# Auxiliary_Regulators.net
KiCad netlist of a schematic drawn in Altium Designer
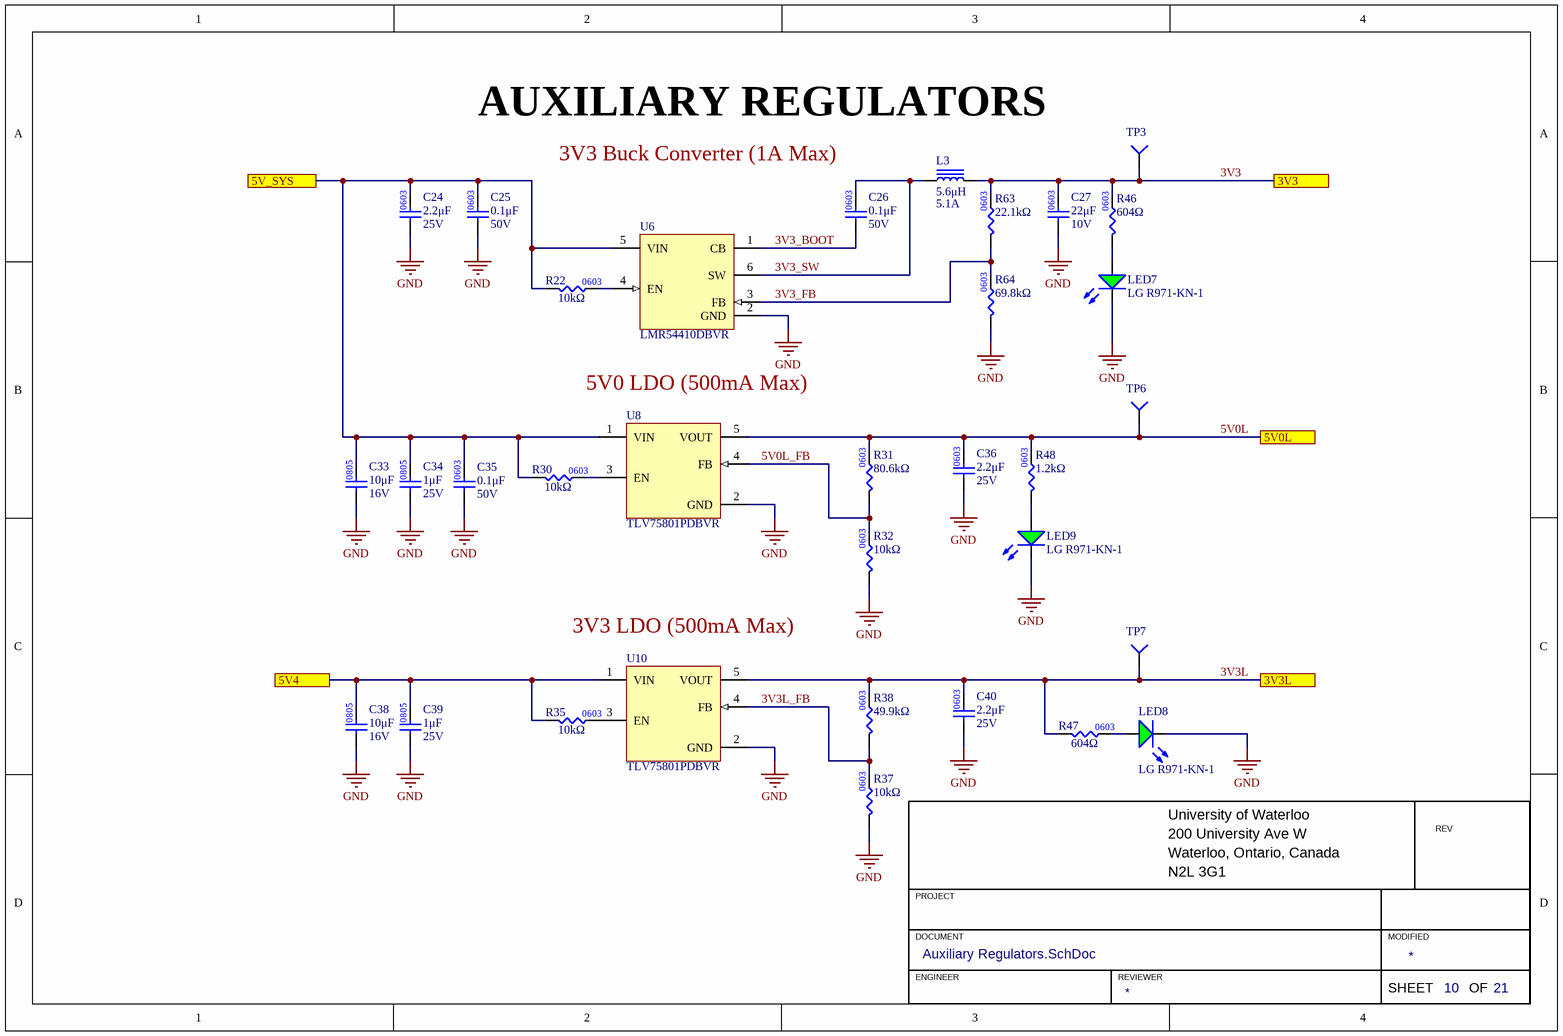
[diagram p0: Auxiliary Regulators.SchDoc]

(export (version "E")
  (design (tool "Eeschema 10.0.6"))
  (components
    (comp (ref "C24")
      (value "2.2μF")
      (footprint "CAP0603")
      (description "CAP CER 2.2UF 25V X5R 0603")
      (fields (field (name "VOLTAGE RATING") "25V") (field (name "Comment") "CAP_2.2uF_25V_0603"))
      (libsource (lib "Personal_Schematic_Library_2022") (part "CAP_2.2uF_25V_0603"))
    )
    (comp (ref "C25")
      (value "0.1μF")
      (footprint "CAP0603")
      (description "CAP CER 0.1UF 50V X7R 0603")
      (fields (field (name "VOLTAGE RATING") "50V") (field (name "Comment") "CAP_0.1uF_50V_0603"))
      (libsource (lib "Personal_Schematic_Library_2022") (part "CAP_0.1uF_50V_0603"))
    )
    (comp (ref "C26")
      (value "0.1μF")
      (footprint "CAP0603")
      (description "CAP CER 0.1UF 50V X7R 0603")
      (fields (field (name "VOLTAGE RATING") "50V") (field (name "Comment") "CAP_0.1uF_50V_0603"))
      (libsource (lib "Personal_Schematic_Library_2022") (part "CAP_0.1uF_50V_0603"))
    )
    (comp (ref "C27")
      (value "22μF")
      (footprint "CAP0603")
      (description "CAP CER 22UF 10V X5R 0603")
      (fields
        (field (name "MANUFACTURER") "Taiyo Yuden")
        (field (name "MANUFACTURER PART NUMBER") "LMK107BBJ226MA-T")
        (field (name "VOLTAGE RATING") "10V")
      )
      (libsource (lib "Personal_Schematic_Library_2022") (part "CAP_22uF_10V_0603"))
    )
    (comp (ref "C33")
      (value "10μF")
      (footprint "CAP0805")
      (description "CAP CER 10UF 16V X5R 0805")
      (fields (field (name "VOLTAGE RATING") "16V") (field (name "Comment") "CAP_10uF_16V_0805"))
      (libsource (lib "Personal_Schematic_Library_2022") (part "CAP_10uF_16V_0805"))
    )
    (comp (ref "C34")
      (value "1μF")
      (footprint "CAP0805")
      (description "CAP CER 1UF 25V X7R 0805")
      (fields (field (name "VOLTAGE RATING") "25V") (field (name "Comment") "CAP_1uF_25V_0805"))
      (libsource (lib "Personal_Schematic_Library_2022") (part "CAP_1uF_25V_0805"))
    )
    (comp (ref "C35")
      (value "0.1μF")
      (footprint "CAP0603")
      (description "CAP CER 0.1UF 50V X7R 0603")
      (fields (field (name "VOLTAGE RATING") "50V") (field (name "Comment") "CAP_0.1uF_50V_0603"))
      (libsource (lib "Personal_Schematic_Library_2022") (part "CAP_0.1uF_50V_0603"))
    )
    (comp (ref "C36")
      (value "2.2μF")
      (footprint "CAP0603")
      (description "CAP CER 2.2UF 25V X5R 0603")
      (fields (field (name "VOLTAGE RATING") "25V") (field (name "Comment") "CAP_2.2uF_25V_0603"))
      (libsource (lib "Personal_Schematic_Library_2022") (part "CAP_2.2uF_25V_0603"))
    )
    (comp (ref "C38")
      (value "10μF")
      (footprint "CAP0805")
      (description "CAP CER 10UF 16V X5R 0805")
      (fields (field (name "VOLTAGE RATING") "16V") (field (name "Comment") "CAP_10uF_16V_0805"))
      (libsource (lib "Personal_Schematic_Library_2022") (part "CAP_10uF_16V_0805"))
    )
    (comp (ref "C39")
      (value "1μF")
      (footprint "CAP0805")
      (description "CAP CER 1UF 25V X7R 0805")
      (fields (field (name "VOLTAGE RATING") "25V") (field (name "Comment") "CAP_1uF_25V_0805"))
      (libsource (lib "Personal_Schematic_Library_2022") (part "CAP_1uF_25V_0805"))
    )
    (comp (ref "C40")
      (value "2.2μF")
      (footprint "CAP0603")
      (description "CAP CER 2.2UF 25V X5R 0603")
      (fields (field (name "VOLTAGE RATING") "25V") (field (name "Comment") "CAP_2.2uF_25V_0603"))
      (libsource (lib "Personal_Schematic_Library_2022") (part "CAP_2.2uF_25V_0603"))
    )
    (comp (ref "L3")
      (value "IND_5.6uH_5.1A")
      (footprint "IND_WURTH_4040")
      (description "POWER INDUCTOR 4040; 5.6 H; 5.1A")
      (fields (field (name "CURRENT RATING") "5.1A") (field (name "INDUCTANCE") "5.6μH"))
      (libsource (lib "Personal_Schematic_Library_2022") (part "IND_5.6uH_5.1A"))
    )
    (comp (ref "LED7")
      (value "LED_GREEN")
      (footprint "LED_0805_GREEN")
      (description "LED GREEN DIFFUSED 0805 SMD")
      (fields (field (name "MANUFACTURER PART NUMBER 1") "LG R971-KN-1"))
      (libsource (lib "Personal_Schematic_Library_2022") (part "LED_GREEN"))
    )
    (comp (ref "LED8")
      (value "LED_GREEN")
      (footprint "LED_0805_GREEN")
      (description "LED GREEN DIFFUSED 0805 SMD")
      (fields (field (name "MANUFACTURER PART NUMBER 1") "LG R971-KN-1"))
      (libsource (lib "Personal_Schematic_Library_2022") (part "LED_GREEN"))
    )
    (comp (ref "LED9")
      (value "LED_GREEN")
      (footprint "LED_0805_GREEN")
      (description "LED GREEN DIFFUSED 0805 SMD")
      (fields (field (name "MANUFACTURER PART NUMBER 1") "LG R971-KN-1"))
      (libsource (lib "Personal_Schematic_Library_2022") (part "LED_GREEN"))
    )
    (comp (ref "R22")
      (value "10kΩ")
      (footprint "RES0603")
      (description "RES 10K OHM 1% 1/8W 0603")
      (fields (field (name "Comment") "RES_10kΩ_0603_1%"))
      (libsource (lib "Personal_Schematic_Library_2022") (part "RES_10kΩ_0603_1%"))
    )
    (comp (ref "R30")
      (value "10kΩ")
      (footprint "RES0603")
      (description "RES 10K OHM 1% 1/8W 0603")
      (fields (field (name "Comment") "RES_10kΩ_0603_1%"))
      (libsource (lib "Personal_Schematic_Library_2022") (part "RES_10kΩ_0603_1%"))
    )
    (comp (ref "R31")
      (value "80.6kΩ")
      (footprint "RES0603")
      (description "RES 80.6K OHM 1% 1/10W 0603")
      (fields (field (name "Comment") "RES_80.6kΩ_0603_1%"))
      (libsource (lib "Personal_Schematic_Library_2022") (part "RES_80.6kΩ_0603_1%"))
    )
    (comp (ref "R32")
      (value "10kΩ")
      (footprint "RES0603")
      (description "RES 10K OHM 1% 1/8W 0603")
      (fields (field (name "Comment") "RES_10kΩ_0603_1%"))
      (libsource (lib "Personal_Schematic_Library_2022") (part "RES_10kΩ_0603_1%"))
    )
    (comp (ref "R35")
      (value "10kΩ")
      (footprint "RES0603")
      (description "RES 10K OHM 1% 1/8W 0603")
      (fields (field (name "Comment") "RES_10kΩ_0603_1%"))
      (libsource (lib "Personal_Schematic_Library_2022") (part "RES_10kΩ_0603_1%"))
    )
    (comp (ref "R37")
      (value "10kΩ")
      (footprint "RES0603")
      (description "RES 10K OHM 1% 1/8W 0603")
      (fields (field (name "Comment") "RES_10kΩ_0603_1%"))
      (libsource (lib "Personal_Schematic_Library_2022") (part "RES_10kΩ_0603_1%"))
    )
    (comp (ref "R38")
      (value "49.9kΩ")
      (footprint "RES0603")
      (description "RES 49.9K OHM 1% 1/10W 0603")
      (fields (field (name "Comment") "RES_49.9kΩ_0603_1%"))
      (libsource (lib "Personal_Schematic_Library_2022") (part "RES_49.9kΩ_0603_1%"))
    )
    (comp (ref "R46")
      (value "604Ω")
      (footprint "RES0603")
      (description "RES 604 OHM 1% 1/10W 0603")
      (fields (field (name "Comment") "RES_604Ω_0603_1%"))
      (libsource (lib "Personal_Schematic_Library_2022") (part "RES_604Ω_0603_1%"))
    )
    (comp (ref "R47")
      (value "604Ω")
      (footprint "RES0603")
      (description "RES 604 OHM 1% 1/10W 0603")
      (fields (field (name "Comment") "RES_604Ω_0603_1%"))
      (libsource (lib "Personal_Schematic_Library_2022") (part "RES_604Ω_0603_1%"))
    )
    (comp (ref "R48")
      (value "1.2kΩ")
      (footprint "RES0603")
      (description "RES 1.2K OHM 1% 1/10W 0603")
      (fields (field (name "Comment") "RES_1.2kΩ_0603_1%"))
      (libsource (lib "Personal_Schematic_Library_2022") (part "RES_1.2kΩ_0603_1%"))
    )
    (comp (ref "R63")
      (value "22.1kΩ")
      (footprint "RES0603")
      (description "RES 22.1K OHM 1% 1/10W 0603")
      (fields (field (name "Comment") "RES_22.1kΩ_0603_1%"))
      (libsource (lib "Personal_Schematic_Library_2022") (part "RES_22.1kΩ_0603_1%"))
    )
    (comp (ref "R64")
      (value "69.8kΩ")
      (footprint "RES0603")
      (description "RES 69.8K OHM 1% 1/10W 0603")
      (fields (field (name "Comment") "RES_69.8kΩ_0603_1%"))
      (libsource (lib "Personal_Schematic_Library_2022") (part "RES_69.8kΩ_0603_1%"))
    )
    (comp (ref "TP3")
      (value "TESTPOINT_KEYSTONE_LOOP")
      (footprint "KEYSTONE_5019")
      (description "PC TEST POINT MINIATURE")
      (libsource (lib "Personal_Schematic_Library_2022") (part "TESTPOINT_KEYSTONE_LOOP"))
    )
    (comp (ref "TP6")
      (value "TESTPOINT_KEYSTONE_LOOP")
      (footprint "KEYSTONE_5019")
      (description "PC TEST POINT MINIATURE")
      (libsource (lib "Personal_Schematic_Library_2022") (part "TESTPOINT_KEYSTONE_LOOP"))
    )
    (comp (ref "TP7")
      (value "TESTPOINT_KEYSTONE_LOOP")
      (footprint "KEYSTONE_5019")
      (description "PC TEST POINT MINIATURE")
      (libsource (lib "Personal_Schematic_Library_2022") (part "TESTPOINT_KEYSTONE_LOOP"))
    )
    (comp (ref "U6")
      (value "LMR54410DBVR")
      (footprint "SOT23-6")
      (description "IC REG BUCK ADJ 1A SOT23-6")
      (libsource (lib "Personal_Schematic_Library_2022") (part "LMR54410DBVR"))
    )
    (comp (ref "U8")
      (value "TLV75801PDBVR")
      (footprint "TI_SOT23-5")
      (description "IC REG LIN POS ADJ 500MA SOT23-5")
      (fields (field (name "MANUFACTURER PART NUMBER 1") "TLV75801PDBVR"))
      (libsource (lib "Personal_Schematic_Library_2022") (part "TLV75801PDBVR"))
    )
    (comp (ref "U10")
      (value "TLV75801PDBVR")
      (footprint "TI_SOT23-5")
      (description "IC REG LIN POS ADJ 500MA SOT23-5")
      (fields (field (name "MANUFACTURER PART NUMBER 1") "TLV75801PDBVR"))
      (libsource (lib "Personal_Schematic_Library_2022") (part "TLV75801PDBVR"))
    )
  )
  (nets
    (net (code "1") (name "/3V3") (class "Default")
      (node (ref "C27") (pin "2") (pinfunction "2_2") (pintype "passive"))
      (node (ref "L3") (pin "2") (pinfunction "2_2") (pintype "passive"))
      (node (ref "R46") (pin "2") (pinfunction "2_2") (pintype "passive"))
      (node (ref "R63") (pin "2") (pinfunction "2_2") (pintype "passive"))
      (node (ref "TP3") (pin "1") (pinfunction "=value_1") (pintype "passive"))
    )
    (net (code "2") (name "/3V3L") (class "Default")
      (node (ref "C40") (pin "2") (pinfunction "2_2") (pintype "passive"))
      (node (ref "R38") (pin "2") (pinfunction "2_2") (pintype "passive"))
      (node (ref "R47") (pin "1") (pinfunction "1_1") (pintype "passive"))
      (node (ref "TP7") (pin "1") (pinfunction "=value_1") (pintype "passive"))
      (node (ref "U10") (pin "5") (pinfunction "VOUT_5") (pintype "power_in"))
    )
    (net (code "3") (name "/3V3L_FB") (class "Default")
      (node (ref "R37") (pin "2") (pinfunction "2_2") (pintype "passive"))
      (node (ref "R38") (pin "1") (pinfunction "1_1") (pintype "passive"))
      (node (ref "U10") (pin "4") (pinfunction "FB_4") (pintype "input"))
    )
    (net (code "4") (name "/3V3_BOOT") (class "Default")
      (node (ref "C26") (pin "1") (pinfunction "1_1") (pintype "passive"))
      (node (ref "U6") (pin "1") (pinfunction "CB_1") (pintype "power_in"))
    )
    (net (code "5") (name "/3V3_FB") (class "Default")
      (node (ref "R63") (pin "1") (pinfunction "1_1") (pintype "passive"))
      (node (ref "R64") (pin "2") (pinfunction "2_2") (pintype "passive"))
      (node (ref "U6") (pin "3") (pinfunction "FB_3") (pintype "input"))
    )
    (net (code "6") (name "/3V3_SW") (class "Default")
      (node (ref "C26") (pin "2") (pinfunction "2_2") (pintype "passive"))
      (node (ref "L3") (pin "1") (pinfunction "1_1") (pintype "passive"))
      (node (ref "U6") (pin "6") (pinfunction "SW_6") (pintype "power_in"))
    )
    (net (code "7") (name "/5V0L") (class "Default")
      (node (ref "C36") (pin "2") (pinfunction "2_2") (pintype "passive"))
      (node (ref "R31") (pin "2") (pinfunction "2_2") (pintype "passive"))
      (node (ref "R48") (pin "2") (pinfunction "2_2") (pintype "passive"))
      (node (ref "TP6") (pin "1") (pinfunction "=value_1") (pintype "passive"))
      (node (ref "U8") (pin "5") (pinfunction "VOUT_5") (pintype "power_in"))
    )
    (net (code "8") (name "/5V0L_FB") (class "Default")
      (node (ref "R31") (pin "1") (pinfunction "1_1") (pintype "passive"))
      (node (ref "R32") (pin "2") (pinfunction "2_2") (pintype "passive"))
      (node (ref "U8") (pin "4") (pinfunction "FB_4") (pintype "input"))
    )
    (net (code "9") (name "/5V4") (class "Default")
      (node (ref "C38") (pin "2") (pinfunction "2_2") (pintype "passive"))
      (node (ref "C39") (pin "2") (pinfunction "2_2") (pintype "passive"))
      (node (ref "R35") (pin "1") (pinfunction "1_1") (pintype "passive"))
      (node (ref "U10") (pin "1") (pinfunction "VIN_1") (pintype "power_in"))
    )
    (net (code "10") (name "/5V_SYS") (class "Default")
      (node (ref "C24") (pin "2") (pinfunction "2_2") (pintype "passive"))
      (node (ref "C25") (pin "2") (pinfunction "2_2") (pintype "passive"))
      (node (ref "C33") (pin "2") (pinfunction "2_2") (pintype "passive"))
      (node (ref "C34") (pin "2") (pinfunction "2_2") (pintype "passive"))
      (node (ref "C35") (pin "2") (pinfunction "2_2") (pintype "passive"))
      (node (ref "R22") (pin "1") (pinfunction "1_1") (pintype "passive"))
      (node (ref "R30") (pin "1") (pinfunction "1_1") (pintype "passive"))
      (node (ref "U6") (pin "5") (pinfunction "VIN_5") (pintype "power_in"))
      (node (ref "U8") (pin "1") (pinfunction "VIN_1") (pintype "power_in"))
    )
    (net (code "11") (name "GND") (class "Default")
      (node (ref "C24") (pin "1") (pinfunction "1_1") (pintype "passive"))
      (node (ref "C25") (pin "1") (pinfunction "1_1") (pintype "passive"))
      (node (ref "C27") (pin "1") (pinfunction "1_1") (pintype "passive"))
      (node (ref "C33") (pin "1") (pinfunction "1_1") (pintype "passive"))
      (node (ref "C34") (pin "1") (pinfunction "1_1") (pintype "passive"))
      (node (ref "C35") (pin "1") (pinfunction "1_1") (pintype "passive"))
      (node (ref "C36") (pin "1") (pinfunction "1_1") (pintype "passive"))
      (node (ref "C38") (pin "1") (pinfunction "1_1") (pintype "passive"))
      (node (ref "C39") (pin "1") (pinfunction "1_1") (pintype "passive"))
      (node (ref "C40") (pin "1") (pinfunction "1_1") (pintype "passive"))
      (node (ref "LED7") (pin "2") (pinfunction "K_2") (pintype "passive"))
      (node (ref "LED8") (pin "2") (pinfunction "K_2") (pintype "passive"))
      (node (ref "LED9") (pin "2") (pinfunction "K_2") (pintype "passive"))
      (node (ref "R32") (pin "1") (pinfunction "1_1") (pintype "passive"))
      (node (ref "R37") (pin "1") (pinfunction "1_1") (pintype "passive"))
      (node (ref "R64") (pin "1") (pinfunction "1_1") (pintype "passive"))
      (node (ref "U10") (pin "2") (pinfunction "GND_2") (pintype "power_in"))
      (node (ref "U6") (pin "2") (pinfunction "GND_2") (pintype "power_in"))
      (node (ref "U8") (pin "2") (pinfunction "GND_2") (pintype "power_in"))
    )
    (net (code "12") (name "Net-(LED7-A)") (class "Default")
      (node (ref "LED7") (pin "1") (pinfunction "A_1") (pintype "passive"))
      (node (ref "R46") (pin "1") (pinfunction "1_1") (pintype "passive"))
    )
    (net (code "13") (name "Net-(LED8-A)") (class "Default")
      (node (ref "LED8") (pin "1") (pinfunction "A_1") (pintype "passive"))
      (node (ref "R47") (pin "2") (pinfunction "2_2") (pintype "passive"))
    )
    (net (code "14") (name "Net-(LED9-A)") (class "Default")
      (node (ref "LED9") (pin "1") (pinfunction "A_1") (pintype "passive"))
      (node (ref "R48") (pin "1") (pinfunction "1_1") (pintype "passive"))
    )
    (net (code "15") (name "Net-(U6-EN)") (class "Default")
      (node (ref "R22") (pin "2") (pinfunction "2_2") (pintype "passive"))
      (node (ref "U6") (pin "4") (pinfunction "EN_4") (pintype "input"))
    )
    (net (code "16") (name "Net-(U8-EN)") (class "Default")
      (node (ref "R30") (pin "2") (pinfunction "2_2") (pintype "passive"))
      (node (ref "U8") (pin "3") (pinfunction "EN_3") (pintype "passive"))
    )
    (net (code "17") (name "Net-(U10-EN)") (class "Default")
      (node (ref "R35") (pin "2") (pinfunction "2_2") (pintype "passive"))
      (node (ref "U10") (pin "3") (pinfunction "EN_3") (pintype "passive"))
    )
  )
)
